# 03_Sensor.net
KiCad netlist of a schematic drawn in Altium Designer
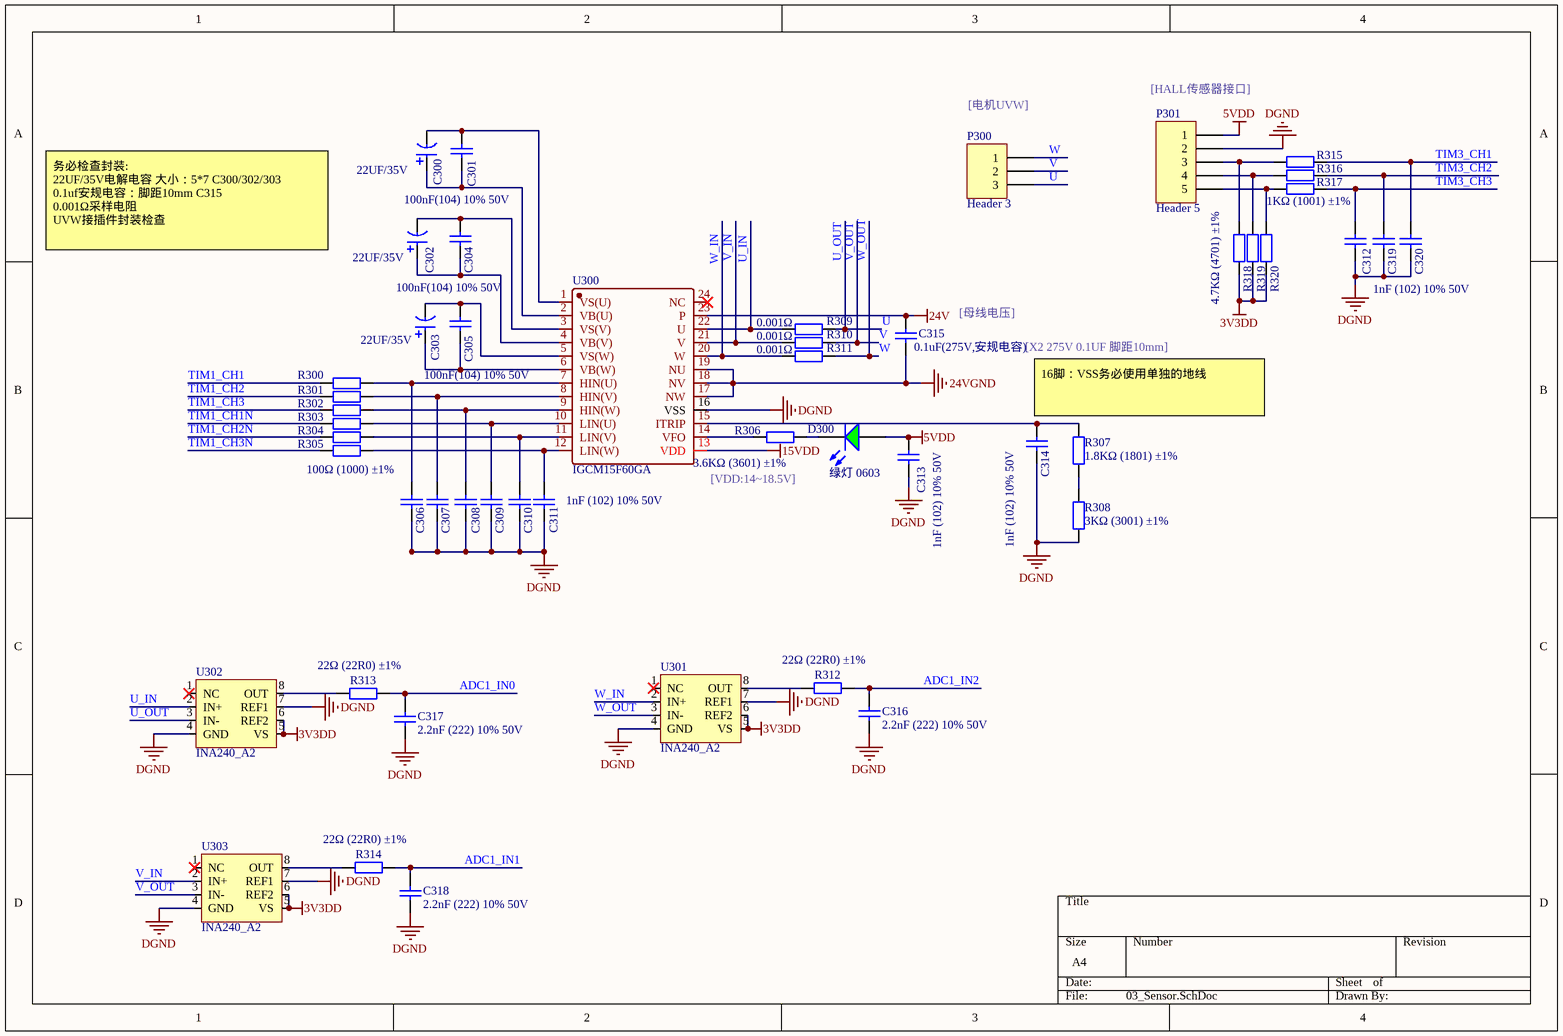
[diagram p0: 03_Sensor.SchDoc]

(export (version "E")
  (design (tool "Eeschema 10.0.6"))
  (components
    (comp (ref "C300")
      (value "22UF/35V")
      (footprint "电解电容5*7")
      (description "电解电容")
      (libsource (lib "Schlibv2") (part "CAP2"))
    )
    (comp (ref "C301")
      (value "100nF(104) 10% 50V")
      (footprint "0805_C")
      (description "贴片电容")
      (libsource (lib "Miscellaneous Devices LC") (part "0805 100nF(104) 10% 50V"))
    )
    (comp (ref "C302")
      (value "22UF/35V")
      (footprint "电解电容5*7")
      (description "电解电容")
      (libsource (lib "Schlibv2") (part "CAP2"))
    )
    (comp (ref "C303")
      (value "22UF/35V")
      (footprint "电解电容5*7")
      (description "电解电容")
      (libsource (lib "Schlibv2") (part "CAP2"))
    )
    (comp (ref "C304")
      (value "100nF(104) 10% 50V")
      (footprint "0805_C")
      (description "贴片电容")
      (libsource (lib "Miscellaneous Devices LC") (part "0805 100nF(104) 10% 50V"))
    )
    (comp (ref "C305")
      (value "100nF(104) 10% 50V")
      (footprint "0805_C")
      (description "贴片电容")
      (libsource (lib "Miscellaneous Devices LC") (part "0805 100nF(104) 10% 50V"))
    )
    (comp (ref "C306")
      (value "1nF (102) 10% 50V")
      (footprint "0603_C")
      (description "贴片电容")
      (libsource (lib "Miscellaneous Devices LC") (part "0603 1nF (102) 10% 50V"))
    )
    (comp (ref "C307")
      (value "1nF (102) 10% 50V")
      (footprint "0603_C")
      (description "贴片电容")
      (libsource (lib "Miscellaneous Devices LC") (part "0603 1nF (102) 10% 50V"))
    )
    (comp (ref "C308")
      (value "1nF (102) 10% 50V")
      (footprint "0603_C")
      (description "贴片电容")
      (libsource (lib "Miscellaneous Devices LC") (part "0603 1nF (102) 10% 50V"))
    )
    (comp (ref "C309")
      (value "1nF (102) 10% 50V")
      (footprint "0603_C")
      (description "贴片电容")
      (libsource (lib "Miscellaneous Devices LC") (part "0603 1nF (102) 10% 50V"))
    )
    (comp (ref "C310")
      (value "1nF (102) 10% 50V")
      (footprint "0603_C")
      (description "贴片电容")
      (libsource (lib "Miscellaneous Devices LC") (part "0603 1nF (102) 10% 50V"))
    )
    (comp (ref "C311")
      (value "1nF (102) 10% 50V")
      (footprint "0603_C")
      (description "贴片电容")
      (libsource (lib "Miscellaneous Devices LC") (part "0603 1nF (102) 10% 50V"))
    )
    (comp (ref "C312")
      (value "1nF (102) 10% 50V")
      (footprint "0603_C")
      (description "贴片电容")
      (libsource (lib "Miscellaneous Devices LC") (part "0603 1nF (102) 10% 50V"))
    )
    (comp (ref "C313")
      (value "1nF (102) 10% 50V")
      (footprint "0603_C")
      (description "贴片电容")
      (libsource (lib "Miscellaneous Devices LC") (part "0603 1nF (102) 10% 50V"))
    )
    (comp (ref "C314")
      (value "1nF (102) 10% 50V")
      (footprint "0603_C")
      (description "贴片电容")
      (libsource (lib "Miscellaneous Devices LC") (part "0603 1nF (102) 10% 50V"))
    )
    (comp (ref "C315")
      (value "0.1uF(275V,安规电容)")
      (footprint "X2_安规电容_10MM")
      (description "贴片电容")
      (libsource (lib "Miscellaneous Devices LC") (part "0603 100nF (104) 10% 50V"))
    )
    (comp (ref "C316")
      (value "2.2nF (222) 10% 50V")
      (footprint "0603_C")
      (description "贴片电容")
      (libsource (lib "Miscellaneous Devices LC") (part "0603 2.2nF (222) 10% 50V"))
    )
    (comp (ref "C317")
      (value "2.2nF (222) 10% 50V")
      (footprint "0603_C")
      (description "贴片电容")
      (libsource (lib "Miscellaneous Devices LC") (part "0603 2.2nF (222) 10% 50V"))
    )
    (comp (ref "C318")
      (value "2.2nF (222) 10% 50V")
      (footprint "0603_C")
      (description "贴片电容")
      (libsource (lib "Miscellaneous Devices LC") (part "0603 2.2nF (222) 10% 50V"))
    )
    (comp (ref "C319")
      (value "1nF (102) 10% 50V")
      (footprint "0603_C")
      (description "贴片电容")
      (libsource (lib "Miscellaneous Devices LC") (part "0603 1nF (102) 10% 50V"))
    )
    (comp (ref "C320")
      (value "1nF (102) 10% 50V")
      (footprint "0603_C")
      (description "贴片电容")
      (libsource (lib "Miscellaneous Devices LC") (part "0603 1nF (102) 10% 50V"))
    )
    (comp (ref "D300")
      (value "绿灯 0603")
      (footprint "0603_LED_S1")
      (description "发光二极管")
      (libsource (lib "Miscellaneous Devices LC") (part "0603 绿灯"))
    )
    (comp (ref "P300")
      (value "Header 3")
      (footprint "KF2EDGK-3.81-WI-3P")
      (description "Header, 3-Pin")
      (fields (field (name "PUBLISHER") "Altium Limited"))
      (libsource (lib "Miscellaneous Connectors") (part "Header 3"))
    )
    (comp (ref "P301")
      (value "Header 5")
      (footprint "KF2EDGK-3.81-WI-5P")
      (description "Header, 5-Pin")
      (fields (field (name "PUBLISHER") "Altium Limited"))
      (libsource (lib "Miscellaneous Connectors") (part "Header 5"))
    )
    (comp (ref "R300")
      (value "100Ω (1000) ±1%")
      (footprint "0603_R")
      (description "贴片电阻")
      (libsource (lib "Miscellaneous Devices LC") (part "0603 100Ω (1000) 1%"))
    )
    (comp (ref "R301")
      (value "100Ω (1000) ±1%")
      (footprint "0603_R")
      (description "贴片电阻")
      (libsource (lib "Miscellaneous Devices LC") (part "0603 100Ω (1000) 1%"))
    )
    (comp (ref "R302")
      (value "100Ω (1000) ±1%")
      (footprint "0603_R")
      (description "贴片电阻")
      (libsource (lib "Miscellaneous Devices LC") (part "0603 100Ω (1000) 1%"))
    )
    (comp (ref "R303")
      (value "100Ω (1000) ±1%")
      (footprint "0603_R")
      (description "贴片电阻")
      (libsource (lib "Miscellaneous Devices LC") (part "0603 100Ω (1000) 1%"))
    )
    (comp (ref "R304")
      (value "100Ω (1000) ±1%")
      (footprint "0603_R")
      (description "贴片电阻")
      (libsource (lib "Miscellaneous Devices LC") (part "0603 100Ω (1000) 1%"))
    )
    (comp (ref "R305")
      (value "100Ω (1000) ±1%")
      (footprint "0603_R")
      (description "贴片电阻")
      (libsource (lib "Miscellaneous Devices LC") (part "0603 100Ω (1000) 1%"))
    )
    (comp (ref "R306")
      (value "3.6KΩ (3601) ±1%")
      (footprint "0603_R")
      (description "贴片电阻")
      (libsource (lib "Miscellaneous Devices LC") (part "0603 3.6KΩ (3601) 1%"))
    )
    (comp (ref "R307")
      (value "1.8KΩ (1801) ±1%")
      (footprint "0603_R")
      (description "贴片电阻")
      (libsource (lib "Miscellaneous Devices LC") (part "0603 1.8KΩ (1801) 1%"))
    )
    (comp (ref "R308")
      (value "3KΩ (3001) ±1%")
      (footprint "0603_R")
      (description "贴片电阻")
      (libsource (lib "Miscellaneous Devices LC") (part "0603 3KΩ (3001) 1%"))
    )
    (comp (ref "R309")
      (value "0.001Ω")
      (footprint "R1206")
      (description "贴片电阻")
      (libsource (lib "Miscellaneous Devices LC") (part "0805 10KΩ (1002) 1%"))
    )
    (comp (ref "R310")
      (value "0.001Ω")
      (footprint "R1206")
      (description "贴片电阻")
      (libsource (lib "Miscellaneous Devices LC") (part "0805 10KΩ (1002) 1%"))
    )
    (comp (ref "R311")
      (value "0.001Ω")
      (footprint "R1206")
      (description "贴片电阻")
      (libsource (lib "Miscellaneous Devices LC") (part "0805 10KΩ (1002) 1%"))
    )
    (comp (ref "R312")
      (value "22Ω (22R0) ±1%")
      (footprint "0603_R")
      (description "贴片电阻")
      (libsource (lib "Miscellaneous Devices LC") (part "0603 22Ω (22R0) 1%"))
    )
    (comp (ref "R313")
      (value "22Ω (22R0) ±1%")
      (footprint "0603_R")
      (description "贴片电阻")
      (libsource (lib "Miscellaneous Devices LC") (part "0603 22Ω (22R0) 1%"))
    )
    (comp (ref "R314")
      (value "22Ω (22R0) ±1%")
      (footprint "0603_R")
      (description "贴片电阻")
      (libsource (lib "Miscellaneous Devices LC") (part "0603 22Ω (22R0) 1%"))
    )
    (comp (ref "R315")
      (value "1KΩ (1001) ±1%")
      (footprint "0603_R")
      (description "贴片电阻")
      (libsource (lib "Miscellaneous Devices LC") (part "0603 1KΩ (1001) 1%"))
    )
    (comp (ref "R316")
      (value "1KΩ (1001) ±1%")
      (footprint "0603_R")
      (description "贴片电阻")
      (libsource (lib "Miscellaneous Devices LC") (part "0603 1KΩ (1001) 1%"))
    )
    (comp (ref "R317")
      (value "1KΩ (1001) ±1%")
      (footprint "0603_R")
      (description "贴片电阻")
      (libsource (lib "Miscellaneous Devices LC") (part "0603 1KΩ (1001) 1%"))
    )
    (comp (ref "R318")
      (value "4.7KΩ (4701) ±1%")
      (footprint "0603_R")
      (description "贴片电阻")
      (libsource (lib "Miscellaneous Devices LC") (part "0603 4.7KΩ (4701) 1%"))
    )
    (comp (ref "R319")
      (value "4.7KΩ (4701) ±1%")
      (footprint "0603_R")
      (description "贴片电阻")
      (libsource (lib "Miscellaneous Devices LC") (part "0603 4.7KΩ (4701) 1%"))
    )
    (comp (ref "R320")
      (value "4.7KΩ (4701) ±1%")
      (footprint "0603_R")
      (description "贴片电阻")
      (libsource (lib "Miscellaneous Devices LC") (part "0603 4.7KΩ (4701) 1%"))
    )
    (comp (ref "U300")
      (value "IGCM15F60GA")
      (footprint "IGCM15F60GA")
      (libsource (lib "Schlibv2") (part "IGCM15F60GA"))
    )
    (comp (ref "U301")
      (value "INA240_A2")
      (footprint "INA240A2PWR")
      (libsource (lib "Schlibv2") (part "INA240_A2"))
    )
    (comp (ref "U302")
      (value "INA240_A2")
      (footprint "INA240A2PWR")
      (libsource (lib "Schlibv2") (part "INA240_A2"))
    )
    (comp (ref "U303")
      (value "INA240_A2")
      (footprint "INA240A2PWR")
      (libsource (lib "Schlibv2") (part "INA240_A2"))
    )
  )
  (nets
    (net (code "1") (name "/ADC1_IN0") (class "Default")
      (node (ref "C317") (pin "2") (pinfunction "2_2") (pintype "passive"))
      (node (ref "R313") (pin "2") (pinfunction "2_2") (pintype "passive"))
    )
    (net (code "2") (name "/ADC1_IN1") (class "Default")
      (node (ref "C318") (pin "2") (pinfunction "2_2") (pintype "passive"))
      (node (ref "R314") (pin "2") (pinfunction "2_2") (pintype "passive"))
    )
    (net (code "3") (name "/ADC1_IN2") (class "Default")
      (node (ref "C316") (pin "2") (pinfunction "2_2") (pintype "passive"))
      (node (ref "R312") (pin "2") (pinfunction "2_2") (pintype "passive"))
    )
    (net (code "4") (name "/TIM1_CH1") (class "Default")
      (node (ref "R300") (pin "1") (pinfunction "1_1") (pintype "passive"))
    )
    (net (code "5") (name "/TIM1_CH1N") (class "Default")
      (node (ref "R303") (pin "1") (pinfunction "1_1") (pintype "passive"))
    )
    (net (code "6") (name "/TIM1_CH2") (class "Default")
      (node (ref "R301") (pin "1") (pinfunction "1_1") (pintype "passive"))
    )
    (net (code "7") (name "/TIM1_CH2N") (class "Default")
      (node (ref "R304") (pin "1") (pinfunction "1_1") (pintype "passive"))
    )
    (net (code "8") (name "/TIM1_CH3") (class "Default")
      (node (ref "R302") (pin "1") (pinfunction "1_1") (pintype "passive"))
    )
    (net (code "9") (name "/TIM1_CH3N") (class "Default")
      (node (ref "R305") (pin "1") (pinfunction "1_1") (pintype "passive"))
    )
    (net (code "10") (name "/TIM3_CH1") (class "Default")
      (node (ref "C320") (pin "2") (pinfunction "2_2") (pintype "passive"))
      (node (ref "R315") (pin "2") (pinfunction "2_2") (pintype "passive"))
    )
    (net (code "11") (name "/TIM3_CH2") (class "Default")
      (node (ref "C319") (pin "2") (pinfunction "2_2") (pintype "passive"))
      (node (ref "R316") (pin "2") (pinfunction "2_2") (pintype "passive"))
    )
    (net (code "12") (name "/TIM3_CH3") (class "Default")
      (node (ref "C312") (pin "2") (pinfunction "2_2") (pintype "passive"))
      (node (ref "R317") (pin "2") (pinfunction "2_2") (pintype "passive"))
    )
    (net (code "13") (name "/U") (class "Default")
      (node (ref "P300") (pin "3") (pinfunction "3_3") (pintype "passive"))
      (node (ref "R309") (pin "2") (pinfunction "2_2") (pintype "passive"))
      (node (ref "U302") (pin "3") (pinfunction "IN-_3") (pintype "passive"))
    )
    (net (code "14") (name "/U_IN") (class "Default")
      (node (ref "R309") (pin "1") (pinfunction "1_1") (pintype "passive"))
      (node (ref "U300") (pin "22") (pinfunction "U_22") (pintype "passive"))
      (node (ref "U302") (pin "2") (pinfunction "IN+_2") (pintype "passive"))
    )
    (net (code "15") (name "/V") (class "Default")
      (node (ref "P300") (pin "2") (pinfunction "2_2") (pintype "passive"))
      (node (ref "R310") (pin "2") (pinfunction "2_2") (pintype "passive"))
      (node (ref "U303") (pin "3") (pinfunction "IN-_3") (pintype "passive"))
    )
    (net (code "16") (name "/V_IN") (class "Default")
      (node (ref "R310") (pin "1") (pinfunction "1_1") (pintype "passive"))
      (node (ref "U300") (pin "21") (pinfunction "V_21") (pintype "passive"))
      (node (ref "U303") (pin "2") (pinfunction "IN+_2") (pintype "passive"))
    )
    (net (code "17") (name "/W") (class "Default")
      (node (ref "P300") (pin "1") (pinfunction "1_1") (pintype "passive"))
      (node (ref "R311") (pin "2") (pinfunction "2_2") (pintype "passive"))
      (node (ref "U301") (pin "3") (pinfunction "IN-_3") (pintype "passive"))
    )
    (net (code "18") (name "/W_IN") (class "Default")
      (node (ref "R311") (pin "1") (pinfunction "1_1") (pintype "passive"))
      (node (ref "U300") (pin "20") (pinfunction "W_20") (pintype "passive"))
      (node (ref "U301") (pin "2") (pinfunction "IN+_2") (pintype "passive"))
    )
    (net (code "19") (name "3V3DD") (class "Default")
      (node (ref "R318") (pin "1") (pinfunction "1_1") (pintype "passive"))
      (node (ref "R319") (pin "1") (pinfunction "1_1") (pintype "passive"))
      (node (ref "R320") (pin "1") (pinfunction "1_1") (pintype "passive"))
      (node (ref "U301") (pin "5") (pinfunction "VS_5") (pintype "passive"))
      (node (ref "U301") (pin "6") (pinfunction "REF2_6") (pintype "passive"))
      (node (ref "U302") (pin "5") (pinfunction "VS_5") (pintype "passive"))
      (node (ref "U302") (pin "6") (pinfunction "REF2_6") (pintype "passive"))
      (node (ref "U303") (pin "5") (pinfunction "VS_5") (pintype "passive"))
      (node (ref "U303") (pin "6") (pinfunction "REF2_6") (pintype "passive"))
    )
    (net (code "20") (name "5VDD") (class "Default")
      (node (ref "C313") (pin "2") (pinfunction "2_2") (pintype "passive"))
      (node (ref "D300") (pin "A") (pinfunction "A_A") (pintype "passive"))
      (node (ref "P301") (pin "1") (pinfunction "1_1") (pintype "passive"))
    )
    (net (code "21") (name "15VDD") (class "Default")
      (node (ref "U300") (pin "13") (pinfunction "VDD_13") (pintype "passive"))
    )
    (net (code "22") (name "24V") (class "Default")
      (node (ref "C315") (pin "2") (pinfunction "2_2") (pintype "passive"))
      (node (ref "U300") (pin "23") (pinfunction "P_23") (pintype "passive"))
    )
    (net (code "23") (name "24VGND") (class "Default")
      (node (ref "C315") (pin "1") (pinfunction "1_1") (pintype "passive"))
      (node (ref "U300") (pin "17") (pinfunction "NW_17") (pintype "passive"))
      (node (ref "U300") (pin "18") (pinfunction "NV_18") (pintype "passive"))
      (node (ref "U300") (pin "19") (pinfunction "NU_19") (pintype "passive"))
    )
    (net (code "24") (name "DGND") (class "Default")
      (node (ref "C306") (pin "1") (pinfunction "1_1") (pintype "passive"))
      (node (ref "C307") (pin "1") (pinfunction "1_1") (pintype "passive"))
      (node (ref "C308") (pin "1") (pinfunction "1_1") (pintype "passive"))
      (node (ref "C309") (pin "1") (pinfunction "1_1") (pintype "passive"))
      (node (ref "C310") (pin "1") (pinfunction "1_1") (pintype "passive"))
      (node (ref "C311") (pin "1") (pinfunction "1_1") (pintype "passive"))
      (node (ref "C312") (pin "1") (pinfunction "1_1") (pintype "passive"))
      (node (ref "C313") (pin "1") (pinfunction "1_1") (pintype "passive"))
      (node (ref "C314") (pin "1") (pinfunction "1_1") (pintype "passive"))
      (node (ref "C316") (pin "1") (pinfunction "1_1") (pintype "passive"))
      (node (ref "C317") (pin "1") (pinfunction "1_1") (pintype "passive"))
      (node (ref "C318") (pin "1") (pinfunction "1_1") (pintype "passive"))
      (node (ref "C319") (pin "1") (pinfunction "1_1") (pintype "passive"))
      (node (ref "C320") (pin "1") (pinfunction "1_1") (pintype "passive"))
      (node (ref "P301") (pin "2") (pinfunction "2_2") (pintype "passive"))
      (node (ref "R308") (pin "1") (pinfunction "1_1") (pintype "passive"))
      (node (ref "U300") (pin "16") (pinfunction "VSS_16") (pintype "passive"))
      (node (ref "U301") (pin "4") (pinfunction "GND_4") (pintype "passive"))
      (node (ref "U301") (pin "7") (pinfunction "REF1_7") (pintype "passive"))
      (node (ref "U302") (pin "4") (pinfunction "GND_4") (pintype "passive"))
      (node (ref "U302") (pin "7") (pinfunction "REF1_7") (pintype "passive"))
      (node (ref "U303") (pin "4") (pinfunction "GND_4") (pintype "passive"))
      (node (ref "U303") (pin "7") (pinfunction "REF1_7") (pintype "passive"))
    )
    (net (code "25") (name "Net-(D300-PadK)") (class "Default")
      (node (ref "D300") (pin "K") (pinfunction "K_K") (pintype "passive"))
      (node (ref "R306") (pin "2") (pinfunction "2_2") (pintype "passive"))
    )
    (net (code "26") (name "Net-(P301-Pad3)") (class "Default")
      (node (ref "P301") (pin "3") (pinfunction "3_3") (pintype "passive"))
      (node (ref "R315") (pin "1") (pinfunction "1_1") (pintype "passive"))
      (node (ref "R318") (pin "2") (pinfunction "2_2") (pintype "passive"))
    )
    (net (code "27") (name "Net-(P301-Pad4)") (class "Default")
      (node (ref "P301") (pin "4") (pinfunction "4_4") (pintype "passive"))
      (node (ref "R316") (pin "1") (pinfunction "1_1") (pintype "passive"))
      (node (ref "R319") (pin "2") (pinfunction "2_2") (pintype "passive"))
    )
    (net (code "28") (name "Net-(P301-Pad5)") (class "Default")
      (node (ref "P301") (pin "5") (pinfunction "5_5") (pintype "passive"))
      (node (ref "R317") (pin "1") (pinfunction "1_1") (pintype "passive"))
      (node (ref "R320") (pin "2") (pinfunction "2_2") (pintype "passive"))
    )
    (net (code "29") (name "Net-(R307-Pad1)") (class "Default")
      (node (ref "R307") (pin "1") (pinfunction "1_1") (pintype "passive"))
      (node (ref "R308") (pin "2") (pinfunction "2_2") (pintype "passive"))
    )
    (net (code "30") (name "Net-(U300-HIN(U))") (class "Default")
      (node (ref "C306") (pin "2") (pinfunction "2_2") (pintype "passive"))
      (node (ref "R300") (pin "2") (pinfunction "2_2") (pintype "passive"))
      (node (ref "U300") (pin "7") (pinfunction "HIN(U)_7") (pintype "passive"))
    )
    (net (code "31") (name "Net-(U300-HIN(V))") (class "Default")
      (node (ref "C307") (pin "2") (pinfunction "2_2") (pintype "passive"))
      (node (ref "R301") (pin "2") (pinfunction "2_2") (pintype "passive"))
      (node (ref "U300") (pin "8") (pinfunction "HIN(V)_8") (pintype "passive"))
    )
    (net (code "32") (name "Net-(U300-HIN(W))") (class "Default")
      (node (ref "C308") (pin "2") (pinfunction "2_2") (pintype "passive"))
      (node (ref "R302") (pin "2") (pinfunction "2_2") (pintype "passive"))
      (node (ref "U300") (pin "9") (pinfunction "HIN(W)_9") (pintype "passive"))
    )
    (net (code "33") (name "Net-(U300-ITRIP)") (class "Default")
      (node (ref "C314") (pin "2") (pinfunction "2_2") (pintype "passive"))
      (node (ref "R307") (pin "2") (pinfunction "2_2") (pintype "passive"))
      (node (ref "U300") (pin "15") (pinfunction "ITRIP_15") (pintype "passive"))
    )
    (net (code "34") (name "Net-(U300-LIN(U))") (class "Default")
      (node (ref "C309") (pin "2") (pinfunction "2_2") (pintype "passive"))
      (node (ref "R303") (pin "2") (pinfunction "2_2") (pintype "passive"))
      (node (ref "U300") (pin "10") (pinfunction "LIN(U)_10") (pintype "passive"))
    )
    (net (code "35") (name "Net-(U300-LIN(V))") (class "Default")
      (node (ref "C310") (pin "2") (pinfunction "2_2") (pintype "passive"))
      (node (ref "R304") (pin "2") (pinfunction "2_2") (pintype "passive"))
      (node (ref "U300") (pin "11") (pinfunction "LIN(V)_11") (pintype "passive"))
    )
    (net (code "36") (name "Net-(U300-LIN(W))") (class "Default")
      (node (ref "C311") (pin "2") (pinfunction "2_2") (pintype "passive"))
      (node (ref "R305") (pin "2") (pinfunction "2_2") (pintype "passive"))
      (node (ref "U300") (pin "12") (pinfunction "LIN(W)_12") (pintype "passive"))
    )
    (net (code "37") (name "Net-(U300-VB(U))") (class "Default")
      (node (ref "C300") (pin "1") (pintype "passive"))
      (node (ref "C301") (pin "1") (pinfunction "1_1") (pintype "passive"))
      (node (ref "U300") (pin "2") (pinfunction "VB(U)_2") (pintype "passive"))
    )
    (net (code "38") (name "Net-(U300-VB(V))") (class "Default")
      (node (ref "C302") (pin "1") (pintype "passive"))
      (node (ref "C304") (pin "1") (pinfunction "1_1") (pintype "passive"))
      (node (ref "U300") (pin "4") (pinfunction "VB(V)_4") (pintype "passive"))
    )
    (net (code "39") (name "Net-(U300-VB(W))") (class "Default")
      (node (ref "C303") (pin "1") (pintype "passive"))
      (node (ref "C305") (pin "1") (pinfunction "1_1") (pintype "passive"))
      (node (ref "U300") (pin "6") (pinfunction "VB(W)_6") (pintype "passive"))
    )
    (net (code "40") (name "Net-(U300-VFO)") (class "Default")
      (node (ref "R306") (pin "1") (pinfunction "1_1") (pintype "passive"))
      (node (ref "U300") (pin "14") (pinfunction "VFO_14") (pintype "passive"))
    )
    (net (code "41") (name "Net-(U300-VS(U))") (class "Default")
      (node (ref "C300") (pin "2") (pintype "passive"))
      (node (ref "C301") (pin "2") (pinfunction "2_2") (pintype "passive"))
      (node (ref "U300") (pin "1") (pinfunction "VS(U)_1") (pintype "passive"))
    )
    (net (code "42") (name "Net-(U300-VS(V))") (class "Default")
      (node (ref "C302") (pin "2") (pintype "passive"))
      (node (ref "C304") (pin "2") (pinfunction "2_2") (pintype "passive"))
      (node (ref "U300") (pin "3") (pinfunction "VS(V)_3") (pintype "passive"))
    )
    (net (code "43") (name "Net-(U300-VS(W))") (class "Default")
      (node (ref "C303") (pin "2") (pintype "passive"))
      (node (ref "C305") (pin "2") (pinfunction "2_2") (pintype "passive"))
      (node (ref "U300") (pin "5") (pinfunction "VS(W)_5") (pintype "passive"))
    )
    (net (code "44") (name "Net-(U301-OUT)") (class "Default")
      (node (ref "R312") (pin "1") (pinfunction "1_1") (pintype "passive"))
      (node (ref "U301") (pin "8") (pinfunction "OUT_8") (pintype "passive"))
    )
    (net (code "45") (name "Net-(U302-OUT)") (class "Default")
      (node (ref "R313") (pin "1") (pinfunction "1_1") (pintype "passive"))
      (node (ref "U302") (pin "8") (pinfunction "OUT_8") (pintype "passive"))
    )
    (net (code "46") (name "Net-(U303-OUT)") (class "Default")
      (node (ref "R314") (pin "1") (pinfunction "1_1") (pintype "passive"))
      (node (ref "U303") (pin "8") (pinfunction "OUT_8") (pintype "passive"))
    )
    (net (code "47") (name "unconnected-(U300-NC-Pad24)") (class "Default")
      (node (ref "U300") (pin "24") (pinfunction "NC_24") (pintype "passive+no_connect"))
    )
    (net (code "48") (name "unconnected-(U301-NC-Pad1)") (class "Default")
      (node (ref "U301") (pin "1") (pinfunction "NC_1") (pintype "passive+no_connect"))
    )
    (net (code "49") (name "unconnected-(U302-NC-Pad1)") (class "Default")
      (node (ref "U302") (pin "1") (pinfunction "NC_1") (pintype "passive+no_connect"))
    )
    (net (code "50") (name "unconnected-(U303-NC-Pad1)") (class "Default")
      (node (ref "U303") (pin "1") (pinfunction "NC_1") (pintype "passive+no_connect"))
    )
  )
)
